# Power_Management.net
KiCad netlist of a schematic drawn in Altium Designer
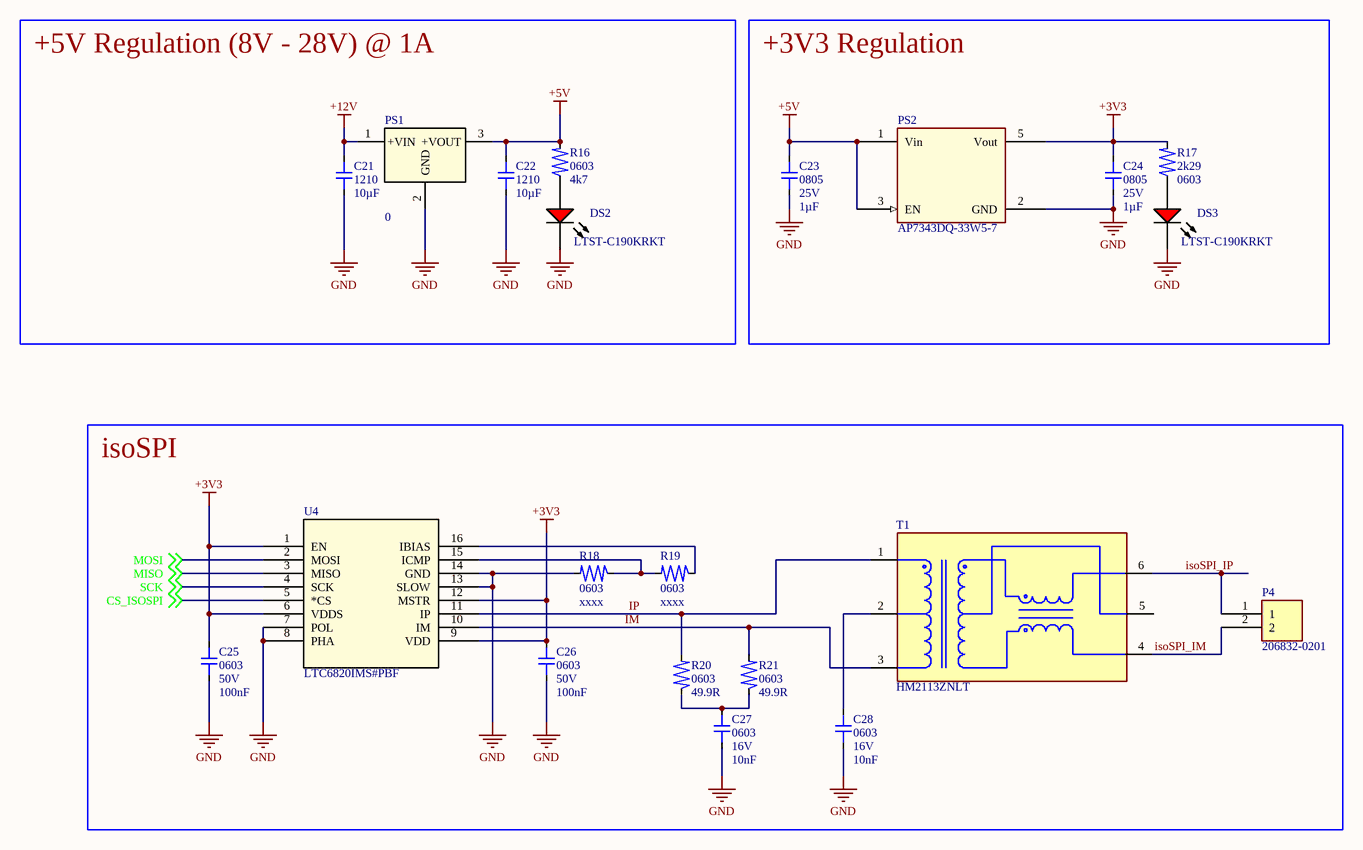
[diagram p0: Power Management.SchDoc]

(export (version "E")
  (design (tool "Eeschema 10.0.6"))
  (components
    (comp (ref "C21")
      (value "10µF")
      (footprint "1210")
      (description "Capacitor 1210")
      (fields (field (name "Comment") "Capacitor 10uF 1210 50V"))
      (libsource (lib "Zips Racing Electric") (part "CAP-0603"))
    )
    (comp (ref "C22")
      (value "10µF")
      (footprint "1210")
      (description "Capacitor 1210")
      (fields (field (name "Comment") "Capacitor 10uF 1210 50V"))
      (libsource (lib "Zips Racing Electric") (part "CAP-0603"))
    )
    (comp (ref "C23")
      (value "1µF")
      (footprint "0805")
      (description "Capacitor, 0805")
      (fields (field (name "VOLTAGE") "25V") (field (name "Comment") "Capacitor 1uF 0805 25V"))
      (libsource (lib "Zips Racing Electric") (part "CAP-0603"))
    )
    (comp (ref "C24")
      (value "1µF")
      (footprint "0805")
      (description "Capacitor, 0805")
      (fields (field (name "VOLTAGE") "25V") (field (name "Comment") "Capacitor 1uF 0805 25V"))
      (libsource (lib "Zips Racing Electric") (part "CAP-0603"))
    )
    (comp (ref "C25")
      (value "100nF")
      (footprint "0603")
      (description "Capacitor, 0603, 5%")
      (fields (field (name "VOLTAGE") "50V") (field (name "Comment") "Capacitor 100nF 0603 5%"))
      (libsource (lib "Zips Racing Electric") (part "CAP-0603"))
    )
    (comp (ref "C26")
      (value "100nF")
      (footprint "0603")
      (description "Capacitor, 0603, 5%")
      (fields (field (name "VOLTAGE") "50V") (field (name "Comment") "Capacitor 100nF 0603 5%"))
      (libsource (lib "Zips Racing Electric") (part "CAP-0603"))
    )
    (comp (ref "C27")
      (value "10nF")
      (footprint "0603")
      (description "Capacitor, 0603, 5%")
      (fields (field (name "VOLTAGE") "16V") (field (name "Comment") "Capacitor 10nF 0603 5%"))
      (libsource (lib "Zips Racing Electric") (part "CAP-0603"))
    )
    (comp (ref "C28")
      (value "10nF")
      (footprint "0603")
      (description "Capacitor, 0603, 5%")
      (fields (field (name "VOLTAGE") "16V") (field (name "Comment") "Capacitor 10nF 0603 5%"))
      (libsource (lib "Zips Racing Electric") (part "CAP-0603"))
    )
    (comp (ref "DS2")
      (value "LTST-C190KRKT")
      (footprint "LTST-C191KRKT_V")
      (description "LED Uni-Color Red, 62.5 mW, 25 mA, -30 to 85 degC, 2-Pin SMD, RoHS, Tape and Reel")
      (fields (field (name "POWER") "75mW") (field (name "MANUFACTURER") "Lite-On"))
      (libsource (lib "Zips Racing Electric") (part "LED-RED-AK-2"))
    )
    (comp (ref "DS3")
      (value "LTST-C190KRKT")
      (footprint "LTST-C191KRKT_V")
      (description "LED Uni-Color Red, 62.5 mW, 25 mA, -30 to 85 degC, 2-Pin SMD, RoHS, Tape and Reel")
      (fields (field (name "POWER") "75mW") (field (name "MANUFACTURER") "Lite-On"))
      (libsource (lib "Zips Racing Electric") (part "LED-RED-AK-2"))
    )
    (comp (ref "P4")
      (value "206832-0201")
      (footprint "FP-206832-0201-MFG")
      (description "Molex, Micro-Fit+, 2 Position, Dual-Row, Header, Male, 3mm Pitch")
      (libsource (lib "Zips Racing Electric") (part "206832-0201"))
    )
    (comp (ref "PS1")
      (value "0")
      (footprint "CONV_R-78E5.0-1.0")
      (description "Linear Regulator Replacement DC DC Converter 1 Output 5V - - 1A 8V - 28V Input")
      (fields
        (field (name "MF") "Recom Power")
        (field (name "MP") "R-78E5.0-1.0")
        (field (name "SOURCE") "Zips_Racing_Electric.SchLib")
      )
      (libsource (lib "Zips Racing Electric") (part "R-78E5.0-1.0"))
    )
    (comp (ref "PS2")
      (value "AP7343DQ-33W5-7")
      (footprint "SOT95P285X140-5N")
      (description "Fixed Positive LDO Regulator")
      (libsource (lib "Zips Racing Electric") (part "AP7343DQ-33W5-7-Symbol-1"))
    )
    (comp (ref "R16")
      (value "4k7")
      (footprint "0603")
      (description "Resistor, 0603, 1%, 1/10W")
      (fields (field (name "TOLERANCE") "1%") (field (name "POWER") "100mW"))
      (libsource (lib "Zips Racing Electric") (part "RES-0603"))
    )
    (comp (ref "R17")
      (value "2k29")
      (footprint "0603")
      (description "Resistor, 0603, 1%, 1/10W")
      (fields (field (name "TOLERANCE") "1%") (field (name "POWER") "100mW"))
      (libsource (lib "Zips Racing Electric") (part "RES-0603"))
    )
    (comp (ref "R18")
      (value "xxxx")
      (footprint "0603")
      (description "Resistor, 0603, 49R9")
      (fields (field (name "TOLERANCE") "1%") (field (name "POWER") "100mW"))
      (libsource (lib "Zips Racing Electric") (part "RES-0603"))
    )
    (comp (ref "R19")
      (value "xxxx")
      (footprint "0603")
      (description "Resistor, 0603, 49R9")
      (fields (field (name "TOLERANCE") "1%") (field (name "POWER") "100mW"))
      (libsource (lib "Zips Racing Electric") (part "RES-0603"))
    )
    (comp (ref "R20")
      (value "49.9R")
      (footprint "0603")
      (description "Resistor, 0603, 49R9")
      (fields (field (name "TOLERANCE") "1%") (field (name "POWER") "100mW"))
      (libsource (lib "Zips Racing Electric") (part "RES-0603"))
    )
    (comp (ref "R21")
      (value "49.9R")
      (footprint "0603")
      (description "Resistor, 0603, 49R9")
      (fields (field (name "TOLERANCE") "1%") (field (name "POWER") "100mW"))
      (libsource (lib "Zips Racing Electric") (part "RES-0603"))
    )
    (comp (ref "T1")
      (value "HM2113ZNLT")
      (footprint "FP-HM2113ZNLT-MFG")
      (description "Datacom Transformer")
      (libsource (lib "Zips Racing Electric") (part "8803d94b0d0e736d1cdfd91e4b934f3"))
    )
    (comp (ref "U4")
      (value "LTC6820IMS#PBF")
      (footprint "MSOP16_MS_ADI")
      (description "Isolated Communications Interface Interface 16-MSOP")
      (fields
        (field (name "SOURCE") "Zips_Racing_Electric.SchLib")
        (field (name "COPYRIGHT") "Copyright (C) 2021 Ultra Librarian. All rights reserved.")
      )
      (libsource (lib "Zips Racing Electric") (part "LTC6820IMS#PBF"))
    )
  )
  (nets
    (net (code "1") (name "+3V3") (class "Default")
      (node (ref "C24") (pin "2") (pinfunction "2_2") (pintype "passive"))
      (node (ref "C25") (pin "2") (pinfunction "2_2") (pintype "passive"))
      (node (ref "C26") (pin "2") (pinfunction "2_2") (pintype "passive"))
      (node (ref "PS2") (pin "5") (pinfunction "Vout_5") (pintype "power_in"))
      (node (ref "R17") (pin "2") (pinfunction "2_2") (pintype "passive"))
      (node (ref "U4") (pin "1") (pinfunction "EN_1") (pintype "passive"))
      (node (ref "U4") (pin "12") (pinfunction "MSTR_12") (pintype "passive"))
      (node (ref "U4") (pin "6") (pinfunction "VDDS_6") (pintype "passive"))
      (node (ref "U4") (pin "9") (pinfunction "VDD_9") (pintype "passive"))
    )
    (net (code "2") (name "+5V") (class "Default")
      (node (ref "C22") (pin "2") (pinfunction "2_2") (pintype "passive"))
      (node (ref "C23") (pin "2") (pinfunction "2_2") (pintype "passive"))
      (node (ref "PS1") (pin "3") (pinfunction "+VOUT_3") (pintype "passive"))
      (node (ref "PS2") (pin "1") (pinfunction "Vin_1") (pintype "power_in"))
      (node (ref "PS2") (pin "3") (pinfunction "EN_3") (pintype "input"))
      (node (ref "R16") (pin "2") (pinfunction "2_2") (pintype "passive"))
    )
    (net (code "3") (name "+12V") (class "Default")
      (node (ref "C21") (pin "2") (pinfunction "2_2") (pintype "passive"))
      (node (ref "PS1") (pin "1") (pinfunction "+VIN_1") (pintype "passive"))
    )
    (net (code "4") (name "/IM") (class "Default")
      (node (ref "R21") (pin "2") (pinfunction "2_2") (pintype "passive"))
      (node (ref "T1") (pin "3") (pinfunction "3_3") (pintype "passive"))
      (node (ref "U4") (pin "10") (pinfunction "IM_10") (pintype "passive"))
    )
    (net (code "5") (name "/IP") (class "Default")
      (node (ref "R20") (pin "2") (pinfunction "2_2") (pintype "passive"))
      (node (ref "T1") (pin "1") (pinfunction "1_1") (pintype "passive"))
      (node (ref "U4") (pin "11") (pinfunction "IP_11") (pintype "passive"))
    )
    (net (code "6") (name "/isoSPI_IM") (class "Default")
      (node (ref "P4") (pin "2") (pinfunction "2_2") (pintype "passive"))
      (node (ref "T1") (pin "4") (pinfunction "4_4") (pintype "passive"))
    )
    (net (code "7") (name "/isoSPI_IP") (class "Default")
      (node (ref "P4") (pin "1") (pinfunction "1_1") (pintype "passive"))
      (node (ref "T1") (pin "6") (pinfunction "6_6") (pintype "passive"))
    )
    (net (code "8") (name "CS_ISOSPI") (class "Default")
      (node (ref "U4") (pin "5") (pinfunction "*CS_5") (pintype "passive"))
    )
    (net (code "9") (name "GND") (class "Default")
      (node (ref "C21") (pin "1") (pinfunction "1_1") (pintype "passive"))
      (node (ref "C22") (pin "1") (pinfunction "1_1") (pintype "passive"))
      (node (ref "C23") (pin "1") (pinfunction "1_1") (pintype "passive"))
      (node (ref "C24") (pin "1") (pinfunction "1_1") (pintype "passive"))
      (node (ref "C25") (pin "1") (pinfunction "1_1") (pintype "passive"))
      (node (ref "C26") (pin "1") (pinfunction "1_1") (pintype "passive"))
      (node (ref "C27") (pin "1") (pinfunction "1_1") (pintype "passive"))
      (node (ref "C28") (pin "1") (pinfunction "1_1") (pintype "passive"))
      (node (ref "DS2") (pin "2") (pinfunction "K_2") (pintype "passive"))
      (node (ref "DS3") (pin "2") (pinfunction "K_2") (pintype "passive"))
      (node (ref "PS1") (pin "2") (pinfunction "GND_2") (pintype "power_in"))
      (node (ref "PS2") (pin "2") (pinfunction "GND_2") (pintype "power_in"))
      (node (ref "R18") (pin "2") (pinfunction "2_2") (pintype "passive"))
      (node (ref "U4") (pin "13") (pinfunction "SLOW_13") (pintype "passive"))
      (node (ref "U4") (pin "14") (pinfunction "GND_14") (pintype "passive"))
      (node (ref "U4") (pin "7") (pinfunction "POL_7") (pintype "passive"))
      (node (ref "U4") (pin "8") (pinfunction "PHA_8") (pintype "passive"))
    )
    (net (code "10") (name "MISO") (class "Default")
      (node (ref "U4") (pin "3") (pinfunction "MISO_3") (pintype "passive"))
    )
    (net (code "11") (name "MOSI") (class "Default")
      (node (ref "U4") (pin "2") (pinfunction "MOSI_2") (pintype "passive"))
    )
    (net (code "12") (name "Net-(C27-Pad2)") (class "Default")
      (node (ref "C27") (pin "2") (pinfunction "2_2") (pintype "passive"))
      (node (ref "R20") (pin "1") (pinfunction "1_1") (pintype "passive"))
      (node (ref "R21") (pin "1") (pinfunction "1_1") (pintype "passive"))
    )
    (net (code "13") (name "Net-(C28-Pad2)") (class "Default")
      (node (ref "C28") (pin "2") (pinfunction "2_2") (pintype "passive"))
      (node (ref "T1") (pin "2") (pinfunction "2_2") (pintype "passive"))
    )
    (net (code "14") (name "Net-(DS2-A)") (class "Default")
      (node (ref "DS2") (pin "1") (pinfunction "A_1") (pintype "passive"))
      (node (ref "R16") (pin "1") (pinfunction "1_1") (pintype "passive"))
    )
    (net (code "15") (name "Net-(DS3-A)") (class "Default")
      (node (ref "DS3") (pin "1") (pinfunction "A_1") (pintype "passive"))
      (node (ref "R17") (pin "1") (pinfunction "1_1") (pintype "passive"))
    )
    (net (code "16") (name "Net-(U4-IBIAS)") (class "Default")
      (node (ref "R19") (pin "1") (pinfunction "1_1") (pintype "passive"))
      (node (ref "U4") (pin "16") (pinfunction "IBIAS_16") (pintype "passive"))
    )
    (net (code "17") (name "Net-(U4-ICMP)") (class "Default")
      (node (ref "R18") (pin "1") (pinfunction "1_1") (pintype "passive"))
      (node (ref "R19") (pin "2") (pinfunction "2_2") (pintype "passive"))
      (node (ref "U4") (pin "15") (pinfunction "ICMP_15") (pintype "passive"))
    )
    (net (code "18") (name "SCK") (class "Default")
      (node (ref "U4") (pin "4") (pinfunction "SCK_4") (pintype "passive"))
    )
    (net (code "19") (name "unconnected-(PS2-NC-Pad4)") (class "Default")
      (node (ref "PS2") (pin "4") (pinfunction "NC_4") (pintype "passive"))
    )
    (net (code "20") (name "unconnected-(T1-Pad5)") (class "Default")
      (node (ref "T1") (pin "5") (pinfunction "5_5") (pintype "passive"))
    )
  )
)
